# MemoryUnit.net
KiCad netlist of a schematic drawn in Altium Designer
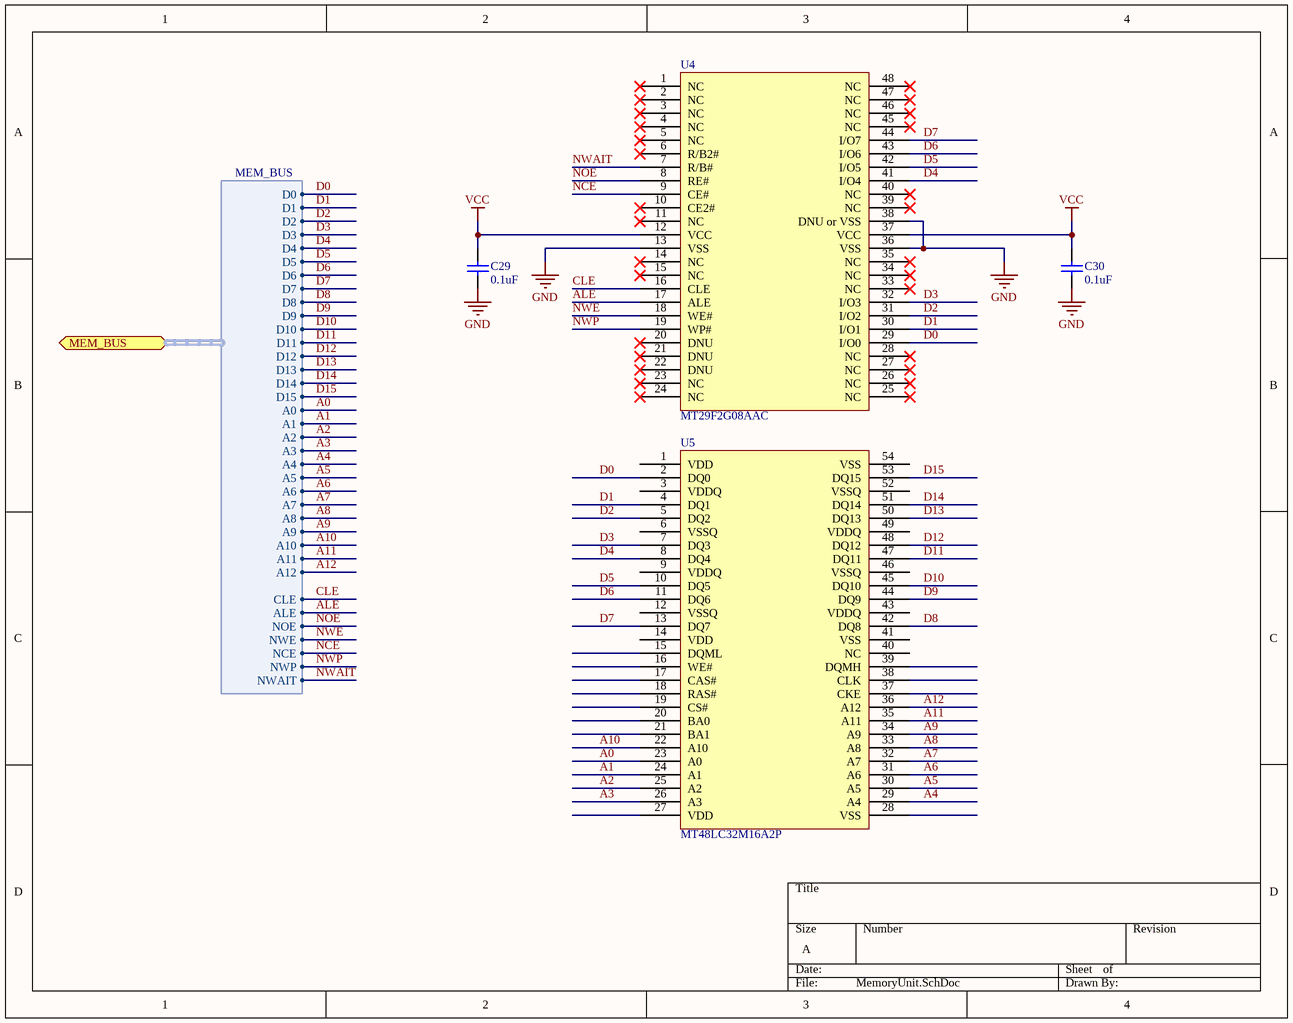
[diagram p0: MemoryUnit.SchDoc]

(export (version "E")
  (design (tool "Eeschema 10.0.6"))
  (components
    (comp (ref "C29")
      (value "0.1uF")
      (footprint "CAP0603")
      (description "Capacitor")
      (fields (field (name "Comment") "ChipCap") (field (name "PUBLISHER") "Altium Limited"))
      (libsource (lib "Common Devices") (part "ChipCap"))
    )
    (comp (ref "C30")
      (value "0.1uF")
      (footprint "CAP0603")
      (description "Capacitor")
      (fields (field (name "Comment") "ChipCap") (field (name "PUBLISHER") "Altium Limited"))
      (libsource (lib "Common Devices") (part "ChipCap"))
    )
    (comp (ref "U4")
      (value "MT29F2G08AAC")
      (footprint "Micron:TSOP-I 48")
      (libsource (lib "Micron") (part "MT29F2G08AAC"))
    )
    (comp (ref "U5")
      (value "MT48LC32M16A2P")
      (footprint "Micron:TSOP-II 54")
      (description "SDRAM 512Mb x16")
      (libsource (lib "Micron") (part "MT48LC32M16A2P"))
    )
  )
  (nets
    (net (code "2") (name "/A0") (class "Default")
      (node (ref "U5") (pin "23") (pinfunction "A0_23") (pintype "passive"))
    )
    (net (code "3") (name "/A1") (class "Default")
      (node (ref "U5") (pin "24") (pinfunction "A1_24") (pintype "passive"))
    )
    (net (code "4") (name "/A2") (class "Default")
      (node (ref "U5") (pin "25") (pinfunction "A2_25") (pintype "passive"))
    )
    (net (code "5") (name "/A3") (class "Default")
      (node (ref "U5") (pin "26") (pinfunction "A3_26") (pintype "passive"))
    )
    (net (code "6") (name "/A4") (class "Default")
      (node (ref "U5") (pin "29") (pinfunction "A4_29") (pintype "passive"))
    )
    (net (code "7") (name "/A5") (class "Default")
      (node (ref "U5") (pin "30") (pinfunction "A5_30") (pintype "passive"))
    )
    (net (code "8") (name "/A6") (class "Default")
      (node (ref "U5") (pin "31") (pinfunction "A6_31") (pintype "passive"))
    )
    (net (code "9") (name "/A7") (class "Default")
      (node (ref "U5") (pin "32") (pinfunction "A7_32") (pintype "passive"))
    )
    (net (code "10") (name "/A8") (class "Default")
      (node (ref "U5") (pin "33") (pinfunction "A8_33") (pintype "passive"))
    )
    (net (code "11") (name "/A9") (class "Default")
      (node (ref "U5") (pin "34") (pinfunction "A9_34") (pintype "passive"))
    )
    (net (code "12") (name "/A10") (class "Default")
      (node (ref "U5") (pin "22") (pinfunction "A10_22") (pintype "passive"))
    )
    (net (code "13") (name "/A11") (class "Default")
      (node (ref "U5") (pin "35") (pinfunction "A11_35") (pintype "passive"))
    )
    (net (code "14") (name "/A12") (class "Default")
      (node (ref "U5") (pin "36") (pinfunction "A12_36") (pintype "passive"))
    )
    (net (code "15") (name "/ALE") (class "Default")
      (node (ref "U4") (pin "17") (pinfunction "ALE_17") (pintype "passive"))
    )
    (net (code "16") (name "/CLE") (class "Default")
      (node (ref "U4") (pin "16") (pinfunction "CLE_16") (pintype "passive"))
    )
    (net (code "17") (name "/D0") (class "Default")
      (node (ref "U4") (pin "29") (pinfunction "I/O0_29") (pintype "passive"))
      (node (ref "U5") (pin "2") (pinfunction "DQ0_2") (pintype "passive"))
    )
    (net (code "18") (name "/D1") (class "Default")
      (node (ref "U4") (pin "30") (pinfunction "I/O1_30") (pintype "passive"))
      (node (ref "U5") (pin "4") (pinfunction "DQ1_4") (pintype "passive"))
    )
    (net (code "19") (name "/D2") (class "Default")
      (node (ref "U4") (pin "31") (pinfunction "I/O2_31") (pintype "passive"))
      (node (ref "U5") (pin "5") (pinfunction "DQ2_5") (pintype "passive"))
    )
    (net (code "20") (name "/D3") (class "Default")
      (node (ref "U4") (pin "32") (pinfunction "I/O3_32") (pintype "passive"))
      (node (ref "U5") (pin "7") (pinfunction "DQ3_7") (pintype "passive"))
    )
    (net (code "21") (name "/D4") (class "Default")
      (node (ref "U4") (pin "41") (pinfunction "I/O4_41") (pintype "passive"))
      (node (ref "U5") (pin "8") (pinfunction "DQ4_8") (pintype "passive"))
    )
    (net (code "22") (name "/D5") (class "Default")
      (node (ref "U4") (pin "42") (pinfunction "I/O5_42") (pintype "passive"))
      (node (ref "U5") (pin "10") (pinfunction "DQ5_10") (pintype "passive"))
    )
    (net (code "23") (name "/D6") (class "Default")
      (node (ref "U4") (pin "43") (pinfunction "I/O6_43") (pintype "passive"))
      (node (ref "U5") (pin "11") (pinfunction "DQ6_11") (pintype "passive"))
    )
    (net (code "24") (name "/D7") (class "Default")
      (node (ref "U4") (pin "44") (pinfunction "I/O7_44") (pintype "passive"))
      (node (ref "U5") (pin "13") (pinfunction "DQ7_13") (pintype "passive"))
    )
    (net (code "25") (name "/D8") (class "Default")
      (node (ref "U5") (pin "42") (pinfunction "DQ8_42") (pintype "passive"))
    )
    (net (code "26") (name "/D9") (class "Default")
      (node (ref "U5") (pin "44") (pinfunction "DQ9_44") (pintype "passive"))
    )
    (net (code "27") (name "/D10") (class "Default")
      (node (ref "U5") (pin "45") (pinfunction "DQ10_45") (pintype "passive"))
    )
    (net (code "28") (name "/D11") (class "Default")
      (node (ref "U5") (pin "47") (pinfunction "DQ11_47") (pintype "passive"))
    )
    (net (code "29") (name "/D12") (class "Default")
      (node (ref "U5") (pin "48") (pinfunction "DQ12_48") (pintype "passive"))
    )
    (net (code "30") (name "/D13") (class "Default")
      (node (ref "U5") (pin "50") (pinfunction "DQ13_50") (pintype "passive"))
    )
    (net (code "31") (name "/D14") (class "Default")
      (node (ref "U5") (pin "51") (pinfunction "DQ14_51") (pintype "passive"))
    )
    (net (code "32") (name "/D15") (class "Default")
      (node (ref "U5") (pin "53") (pinfunction "DQ15_53") (pintype "passive"))
    )
    (net (code "33") (name "/NCE") (class "Default")
      (node (ref "U4") (pin "9") (pinfunction "CE#_9") (pintype "passive"))
    )
    (net (code "34") (name "/NOE") (class "Default")
      (node (ref "U4") (pin "8") (pinfunction "RE#_8") (pintype "passive"))
    )
    (net (code "35") (name "/NWAIT") (class "Default")
      (node (ref "U4") (pin "7") (pinfunction "R/B#_7") (pintype "passive"))
    )
    (net (code "36") (name "/NWE") (class "Default")
      (node (ref "U4") (pin "18") (pinfunction "WE#_18") (pintype "passive"))
    )
    (net (code "37") (name "/NWP") (class "Default")
      (node (ref "U4") (pin "19") (pinfunction "WP#_19") (pintype "passive"))
    )
    (net (code "39") (name "GND") (class "Default")
      (node (ref "C29") (pin "1") (pinfunction "1_1") (pintype "passive"))
      (node (ref "C30") (pin "1") (pinfunction "1_1") (pintype "passive"))
      (node (ref "U4") (pin "13") (pinfunction "VSS_13") (pintype "passive"))
      (node (ref "U4") (pin "36") (pinfunction "VSS_36") (pintype "passive"))
      (node (ref "U4") (pin "38") (pinfunction "DNU_or_VSS_38") (pintype "passive"))
    )
    (net (code "40") (name "VCC") (class "Default")
      (node (ref "C29") (pin "2") (pinfunction "2_2") (pintype "passive"))
      (node (ref "C30") (pin "2") (pinfunction "2_2") (pintype "passive"))
      (node (ref "U4") (pin "12") (pinfunction "VCC_12") (pintype "passive"))
      (node (ref "U4") (pin "37") (pinfunction "VCC_37") (pintype "passive"))
    )
    (net (code "41") (name "unconnected-(U4-CE2#-Pad10)") (class "Default")
      (node (ref "U4") (pin "10") (pinfunction "CE2#_10") (pintype "passive+no_connect"))
    )
    (net (code "42") (name "unconnected-(U4-DNU-Pad20)") (class "Default")
      (node (ref "U4") (pin "20") (pinfunction "DNU_20") (pintype "passive+no_connect"))
    )
    (net (code "43") (name "unconnected-(U4-DNU-Pad21)") (class "Default")
      (node (ref "U4") (pin "21") (pinfunction "DNU_21") (pintype "passive+no_connect"))
    )
    (net (code "44") (name "unconnected-(U4-DNU-Pad22)") (class "Default")
      (node (ref "U4") (pin "22") (pinfunction "DNU_22") (pintype "passive+no_connect"))
    )
    (net (code "45") (name "unconnected-(U4-NC-Pad1)") (class "Default")
      (node (ref "U4") (pin "1") (pinfunction "NC_1") (pintype "passive+no_connect"))
    )
    (net (code "46") (name "unconnected-(U4-NC-Pad2)") (class "Default")
      (node (ref "U4") (pin "2") (pinfunction "NC_2") (pintype "passive+no_connect"))
    )
    (net (code "47") (name "unconnected-(U4-NC-Pad3)") (class "Default")
      (node (ref "U4") (pin "3") (pinfunction "NC_3") (pintype "passive+no_connect"))
    )
    (net (code "48") (name "unconnected-(U4-NC-Pad4)") (class "Default")
      (node (ref "U4") (pin "4") (pinfunction "NC_4") (pintype "passive+no_connect"))
    )
    (net (code "49") (name "unconnected-(U4-NC-Pad5)") (class "Default")
      (node (ref "U4") (pin "5") (pinfunction "NC_5") (pintype "passive+no_connect"))
    )
    (net (code "50") (name "unconnected-(U4-NC-Pad11)") (class "Default")
      (node (ref "U4") (pin "11") (pinfunction "NC_11") (pintype "passive+no_connect"))
    )
    (net (code "51") (name "unconnected-(U4-NC-Pad14)") (class "Default")
      (node (ref "U4") (pin "14") (pinfunction "NC_14") (pintype "passive+no_connect"))
    )
    (net (code "52") (name "unconnected-(U4-NC-Pad15)") (class "Default")
      (node (ref "U4") (pin "15") (pinfunction "NC_15") (pintype "passive+no_connect"))
    )
    (net (code "53") (name "unconnected-(U4-NC-Pad23)") (class "Default")
      (node (ref "U4") (pin "23") (pinfunction "NC_23") (pintype "passive+no_connect"))
    )
    (net (code "54") (name "unconnected-(U4-NC-Pad24)") (class "Default")
      (node (ref "U4") (pin "24") (pinfunction "NC_24") (pintype "passive+no_connect"))
    )
    (net (code "55") (name "unconnected-(U4-NC-Pad25)") (class "Default")
      (node (ref "U4") (pin "25") (pinfunction "NC_25") (pintype "passive+no_connect"))
    )
    (net (code "56") (name "unconnected-(U4-NC-Pad26)") (class "Default")
      (node (ref "U4") (pin "26") (pinfunction "NC_26") (pintype "passive+no_connect"))
    )
    (net (code "57") (name "unconnected-(U4-NC-Pad27)") (class "Default")
      (node (ref "U4") (pin "27") (pinfunction "NC_27") (pintype "passive+no_connect"))
    )
    (net (code "58") (name "unconnected-(U4-NC-Pad28)") (class "Default")
      (node (ref "U4") (pin "28") (pinfunction "NC_28") (pintype "passive+no_connect"))
    )
    (net (code "59") (name "unconnected-(U4-NC-Pad33)") (class "Default")
      (node (ref "U4") (pin "33") (pinfunction "NC_33") (pintype "passive+no_connect"))
    )
    (net (code "60") (name "unconnected-(U4-NC-Pad34)") (class "Default")
      (node (ref "U4") (pin "34") (pinfunction "NC_34") (pintype "passive+no_connect"))
    )
    (net (code "61") (name "unconnected-(U4-NC-Pad35)") (class "Default")
      (node (ref "U4") (pin "35") (pinfunction "NC_35") (pintype "passive+no_connect"))
    )
    (net (code "62") (name "unconnected-(U4-NC-Pad39)") (class "Default")
      (node (ref "U4") (pin "39") (pinfunction "NC_39") (pintype "passive+no_connect"))
    )
    (net (code "63") (name "unconnected-(U4-NC-Pad40)") (class "Default")
      (node (ref "U4") (pin "40") (pinfunction "NC_40") (pintype "passive+no_connect"))
    )
    (net (code "64") (name "unconnected-(U4-NC-Pad45)") (class "Default")
      (node (ref "U4") (pin "45") (pinfunction "NC_45") (pintype "passive+no_connect"))
    )
    (net (code "65") (name "unconnected-(U4-NC-Pad46)") (class "Default")
      (node (ref "U4") (pin "46") (pinfunction "NC_46") (pintype "passive+no_connect"))
    )
    (net (code "66") (name "unconnected-(U4-NC-Pad47)") (class "Default")
      (node (ref "U4") (pin "47") (pinfunction "NC_47") (pintype "passive+no_connect"))
    )
    (net (code "67") (name "unconnected-(U4-NC-Pad48)") (class "Default")
      (node (ref "U4") (pin "48") (pinfunction "NC_48") (pintype "passive+no_connect"))
    )
    (net (code "68") (name "unconnected-(U4-R{slash}B2#-Pad6)") (class "Default")
      (node (ref "U4") (pin "6") (pinfunction "R/B2#_6") (pintype "passive+no_connect"))
    )
    (net (code "69") (name "unconnected-(U5-BA0-Pad20)") (class "Default")
      (node (ref "U5") (pin "20") (pinfunction "BA0_20") (pintype "passive"))
    )
    (net (code "70") (name "unconnected-(U5-BA1-Pad21)") (class "Default")
      (node (ref "U5") (pin "21") (pinfunction "BA1_21") (pintype "passive"))
    )
    (net (code "71") (name "unconnected-(U5-CAS#-Pad17)") (class "Default")
      (node (ref "U5") (pin "17") (pinfunction "CAS#_17") (pintype "passive"))
    )
    (net (code "72") (name "unconnected-(U5-CKE-Pad37)") (class "Default")
      (node (ref "U5") (pin "37") (pinfunction "CKE_37") (pintype "passive"))
    )
    (net (code "73") (name "unconnected-(U5-CLK-Pad38)") (class "Default")
      (node (ref "U5") (pin "38") (pinfunction "CLK_38") (pintype "passive"))
    )
    (net (code "74") (name "unconnected-(U5-CS#-Pad19)") (class "Default")
      (node (ref "U5") (pin "19") (pinfunction "CS#_19") (pintype "passive"))
    )
    (net (code "75") (name "unconnected-(U5-DQMH-Pad39)") (class "Default")
      (node (ref "U5") (pin "39") (pinfunction "DQMH_39") (pintype "passive"))
    )
    (net (code "76") (name "unconnected-(U5-DQML-Pad15)") (class "Default")
      (node (ref "U5") (pin "15") (pinfunction "DQML_15") (pintype "passive"))
    )
    (net (code "77") (name "unconnected-(U5-NC-Pad40)") (class "Default")
      (node (ref "U5") (pin "40") (pinfunction "NC_40") (pintype "passive"))
    )
    (net (code "78") (name "unconnected-(U5-RAS#-Pad18)") (class "Default")
      (node (ref "U5") (pin "18") (pinfunction "RAS#_18") (pintype "passive"))
    )
    (net (code "79") (name "unconnected-(U5-VDD-Pad1)") (class "Default")
      (node (ref "U5") (pin "1") (pinfunction "VDD_1") (pintype "passive"))
    )
    (net (code "80") (name "unconnected-(U5-VDD-Pad14)") (class "Default")
      (node (ref "U5") (pin "14") (pinfunction "VDD_14") (pintype "passive"))
    )
    (net (code "81") (name "unconnected-(U5-VDD-Pad27)") (class "Default")
      (node (ref "U5") (pin "27") (pinfunction "VDD_27") (pintype "passive"))
    )
    (net (code "82") (name "unconnected-(U5-VDDQ-Pad3)") (class "Default")
      (node (ref "U5") (pin "3") (pinfunction "VDDQ_3") (pintype "passive"))
    )
    (net (code "83") (name "unconnected-(U5-VDDQ-Pad9)") (class "Default")
      (node (ref "U5") (pin "9") (pinfunction "VDDQ_9") (pintype "passive"))
    )
    (net (code "84") (name "unconnected-(U5-VDDQ-Pad43)") (class "Default")
      (node (ref "U5") (pin "43") (pinfunction "VDDQ_43") (pintype "passive"))
    )
    (net (code "85") (name "unconnected-(U5-VDDQ-Pad49)") (class "Default")
      (node (ref "U5") (pin "49") (pinfunction "VDDQ_49") (pintype "passive"))
    )
    (net (code "86") (name "unconnected-(U5-VSS-Pad28)") (class "Default")
      (node (ref "U5") (pin "28") (pinfunction "VSS_28") (pintype "passive"))
    )
    (net (code "87") (name "unconnected-(U5-VSS-Pad41)") (class "Default")
      (node (ref "U5") (pin "41") (pinfunction "VSS_41") (pintype "passive"))
    )
    (net (code "88") (name "unconnected-(U5-VSS-Pad54)") (class "Default")
      (node (ref "U5") (pin "54") (pinfunction "VSS_54") (pintype "passive"))
    )
    (net (code "89") (name "unconnected-(U5-VSSQ-Pad6)") (class "Default")
      (node (ref "U5") (pin "6") (pinfunction "VSSQ_6") (pintype "passive"))
    )
    (net (code "90") (name "unconnected-(U5-VSSQ-Pad12)") (class "Default")
      (node (ref "U5") (pin "12") (pinfunction "VSSQ_12") (pintype "passive"))
    )
    (net (code "91") (name "unconnected-(U5-VSSQ-Pad46)") (class "Default")
      (node (ref "U5") (pin "46") (pinfunction "VSSQ_46") (pintype "passive"))
    )
    (net (code "92") (name "unconnected-(U5-VSSQ-Pad52)") (class "Default")
      (node (ref "U5") (pin "52") (pinfunction "VSSQ_52") (pintype "passive"))
    )
    (net (code "93") (name "unconnected-(U5-WE#-Pad16)") (class "Default")
      (node (ref "U5") (pin "16") (pinfunction "WE#_16") (pintype "passive"))
    )
  )
)
